# babyGroot.net
KiCad netlist of a schematic drawn in EAGLE
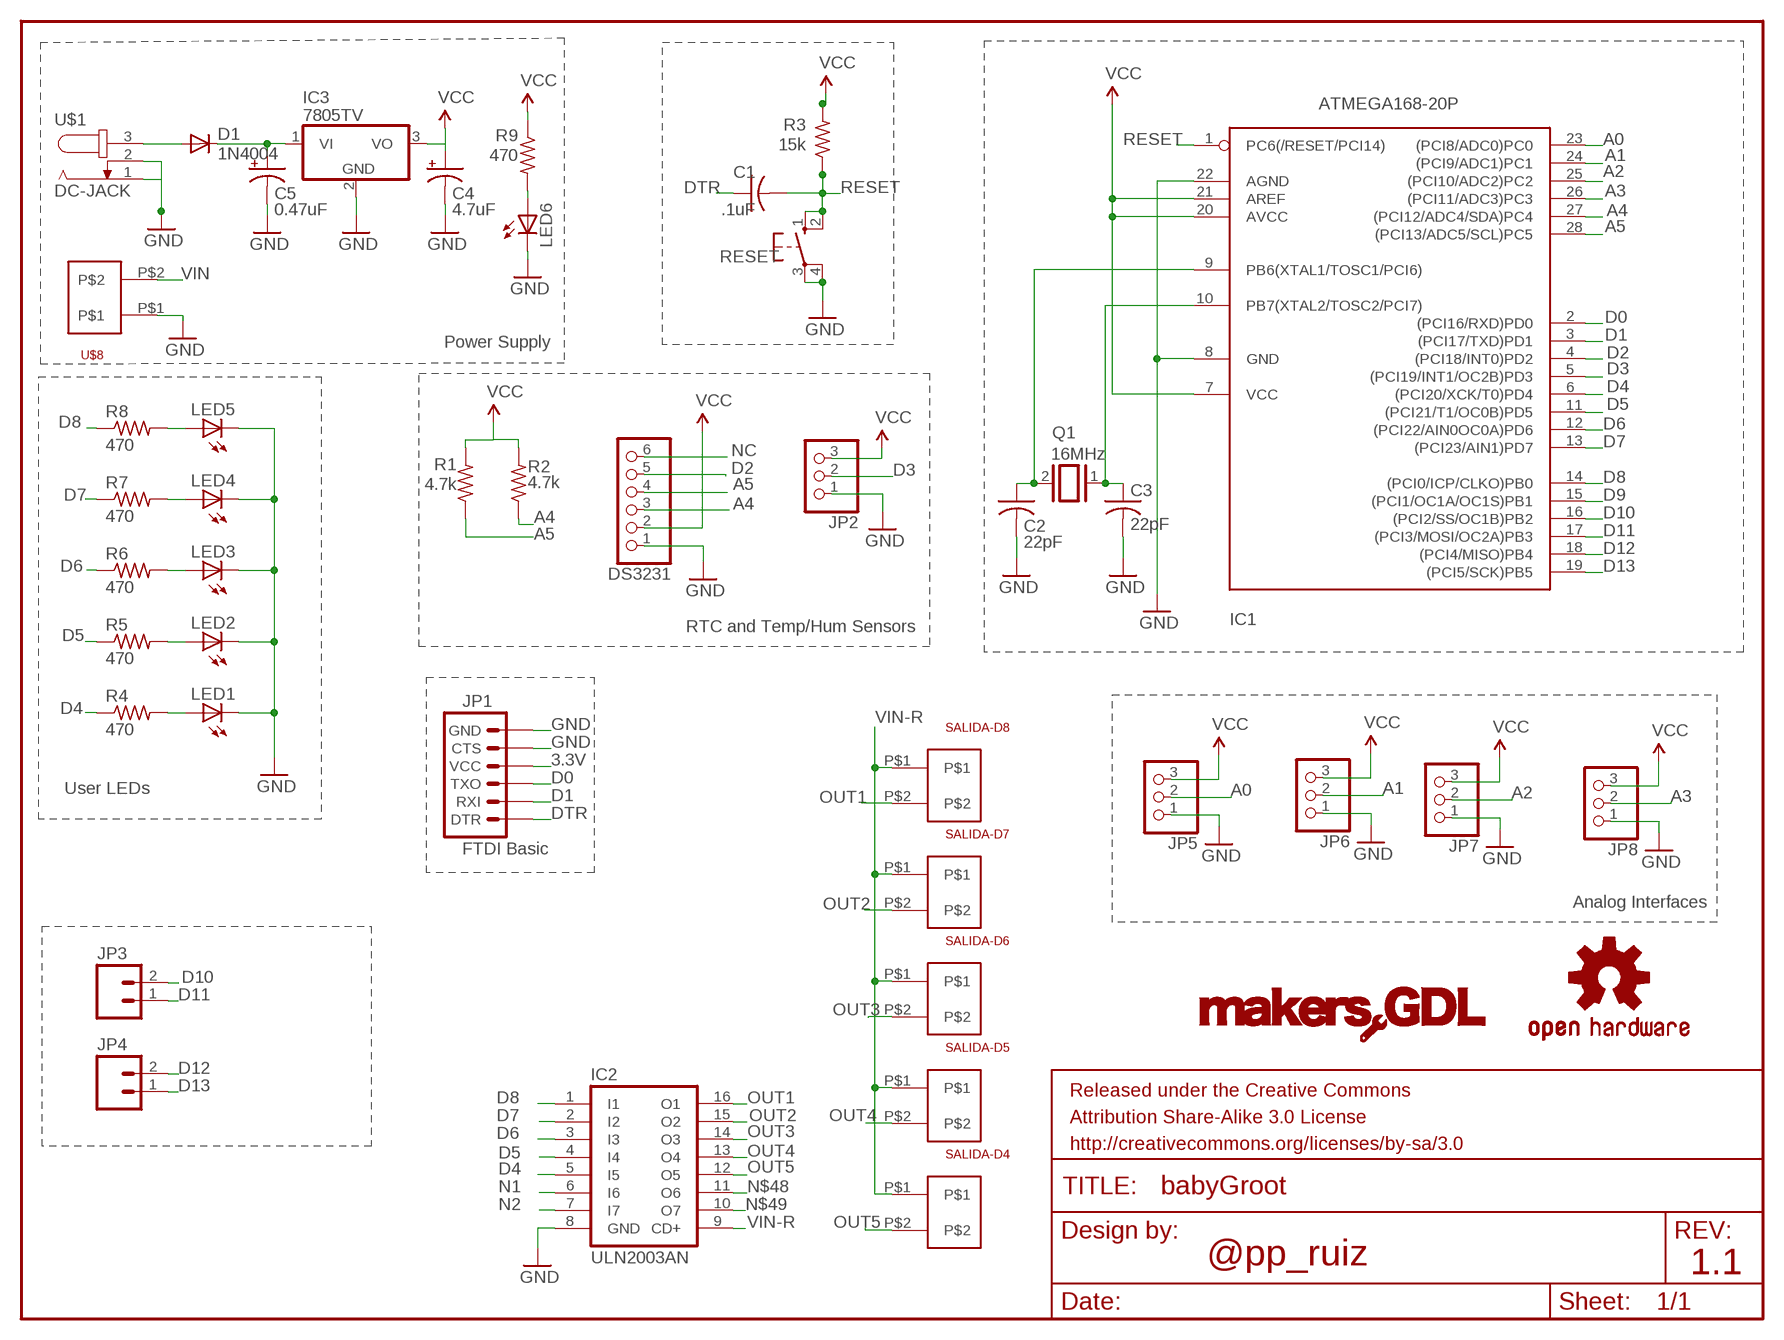
[diagram p0: schematic, sheet 1]

(export (version "E")
  (design (tool "Eeschema 10.0.6"))
  (components
    (comp (ref "C1")
      (value ".1uF")
      (footprint "eagle-import:C025-024X044")
      (libsource (lib "eagle-import") (part "C-US025-024X044"))
    )
    (comp (ref "C2")
      (value "22pF")
      (footprint "eagle-import:C025-024X044")
      (libsource (lib "eagle-import") (part "C-US025-024X044"))
    )
    (comp (ref "C3")
      (value "22pF")
      (footprint "eagle-import:C025-024X044")
      (libsource (lib "eagle-import") (part "C-US025-024X044"))
    )
    (comp (ref "C4")
      (value "4.7uF")
      (footprint "eagle-import:E2,5-6E")
      (libsource (lib "eagle-import") (part "CPOL-USE2,5-6E"))
    )
    (comp (ref "C5")
      (value "0.47uF")
      (footprint "eagle-import:E2,5-6E")
      (libsource (lib "eagle-import") (part "CPOL-USE2,5-6E"))
    )
    (comp (ref "D1")
      (value "1N4004")
      (footprint "eagle-import:DO41-10")
      (libsource (lib "eagle-import") (part "1N4004"))
    )
    (comp (ref "DS3231")
      (value "PINHD-1X6")
      (footprint "eagle-import:1X06")
      (libsource (lib "eagle-import") (part "PINHD-1X6"))
    )
    (comp (ref "FRAME1")
      (value "FRAME-LETTER")
      (footprint "eagle-import:CREATIVE_COMMONS")
      (libsource (lib "eagle-import") (part "FRAME-LETTER"))
    )
    (comp (ref "IC1")
      (value "ATMEGA168-20P")
      (footprint "eagle-import:DIL28-3")
      (libsource (lib "eagle-import") (part "ATMEGA168P-20"))
    )
    (comp (ref "IC2")
      (value "ULN2003AN")
      (footprint "eagle-import:DIL16")
      (libsource (lib "eagle-import") (part "ULN2003AN"))
    )
    (comp (ref "IC3")
      (value "7805TV")
      (footprint "eagle-import:TO220V")
      (libsource (lib "eagle-import") (part "78TV05"))
    )
    (comp (ref "JP1")
      (value "FTDI Basic")
      (footprint "eagle-import:1X06")
      (libsource (lib "eagle-import") (part "ARDUINO_SERIAL_PROGRAMPTH"))
    )
    (comp (ref "JP2")
      (value "PINHD-1X3")
      (footprint "eagle-import:1X03")
      (libsource (lib "eagle-import") (part "PINHD-1X3"))
    )
    (comp (ref "JP3")
      (value "M02PTH")
      (footprint "eagle-import:1X02")
      (libsource (lib "eagle-import") (part "M02PTH"))
    )
    (comp (ref "JP4")
      (value "M02PTH")
      (footprint "eagle-import:1X02")
      (libsource (lib "eagle-import") (part "M02PTH"))
    )
    (comp (ref "JP5")
      (value "PINHD-1X3")
      (footprint "eagle-import:1X03")
      (libsource (lib "eagle-import") (part "PINHD-1X3"))
    )
    (comp (ref "JP6")
      (value "PINHD-1X3")
      (footprint "eagle-import:1X03")
      (libsource (lib "eagle-import") (part "PINHD-1X3"))
    )
    (comp (ref "JP7")
      (value "PINHD-1X3")
      (footprint "eagle-import:1X03")
      (libsource (lib "eagle-import") (part "PINHD-1X3"))
    )
    (comp (ref "JP8")
      (value "PINHD-1X3")
      (footprint "eagle-import:1X03")
      (libsource (lib "eagle-import") (part "PINHD-1X3"))
    )
    (comp (ref "LED1")
      (value "LED3MM")
      (footprint "eagle-import:LED3MM")
      (libsource (lib "eagle-import") (part "LED3MM"))
    )
    (comp (ref "LED2")
      (value "LED3MM")
      (footprint "eagle-import:LED3MM")
      (libsource (lib "eagle-import") (part "LED3MM"))
    )
    (comp (ref "LED3")
      (value "LED3MM")
      (footprint "eagle-import:LED3MM")
      (libsource (lib "eagle-import") (part "LED3MM"))
    )
    (comp (ref "LED4")
      (value "LED3MM")
      (footprint "eagle-import:LED3MM")
      (libsource (lib "eagle-import") (part "LED3MM"))
    )
    (comp (ref "LED5")
      (value "LED3MM")
      (footprint "eagle-import:LED3MM")
      (libsource (lib "eagle-import") (part "LED3MM"))
    )
    (comp (ref "LED6")
      (value "LED3MM")
      (footprint "eagle-import:LED3MM")
      (libsource (lib "eagle-import") (part "LED3MM"))
    )
    (comp (ref "Q1")
      (value "16MHz")
      (footprint "eagle-import:QS")
      (libsource (lib "eagle-import") (part "XTAL/S"))
    )
    (comp (ref "R1")
      (value "4.7k")
      (footprint "eagle-import:0204V")
      (libsource (lib "eagle-import") (part "R-US_0204/2V"))
    )
    (comp (ref "R2")
      (value "4.7k")
      (footprint "eagle-import:0204V")
      (libsource (lib "eagle-import") (part "R-US_0204/2V"))
    )
    (comp (ref "R3")
      (value "15k")
      (footprint "eagle-import:0204V")
      (libsource (lib "eagle-import") (part "R-US_0204/2V"))
    )
    (comp (ref "R4")
      (value "470")
      (footprint "eagle-import:0204V")
      (libsource (lib "eagle-import") (part "R-US_0204/2V"))
    )
    (comp (ref "R5")
      (value "470")
      (footprint "eagle-import:0204V")
      (libsource (lib "eagle-import") (part "R-US_0204/2V"))
    )
    (comp (ref "R6")
      (value "470")
      (footprint "eagle-import:0204V")
      (libsource (lib "eagle-import") (part "R-US_0204/2V"))
    )
    (comp (ref "R7")
      (value "470")
      (footprint "eagle-import:0204V")
      (libsource (lib "eagle-import") (part "R-US_0204/2V"))
    )
    (comp (ref "R8")
      (value "470")
      (footprint "eagle-import:0204V")
      (libsource (lib "eagle-import") (part "R-US_0204/2V"))
    )
    (comp (ref "R9")
      (value "470")
      (footprint "eagle-import:0204V")
      (libsource (lib "eagle-import") (part "R-US_0204/2V"))
    )
    (comp (ref "RESET")
      (value "10-XX")
      (footprint "eagle-import:B3F-10XX")
      (fields (field (name "MPN") "B3F-1000"))
      (libsource (lib "eagle-import") (part "10-XX"))
    )
    (comp (ref "SALIDA-D4")
      (value "2POSHEADER-0.5MM")
      (footprint "eagle-import:2PIN-0.5MM")
      (libsource (lib "eagle-import") (part "2POSHEADER-0.5MM"))
    )
    (comp (ref "SALIDA-D5")
      (value "2POSHEADER-0.5MM")
      (footprint "eagle-import:2PIN-0.5MM")
      (libsource (lib "eagle-import") (part "2POSHEADER-0.5MM"))
    )
    (comp (ref "SALIDA-D6")
      (value "2POSHEADER-0.5MM")
      (footprint "eagle-import:2PIN-0.5MM")
      (libsource (lib "eagle-import") (part "2POSHEADER-0.5MM"))
    )
    (comp (ref "SALIDA-D7")
      (value "2POSHEADER-0.5MM")
      (footprint "eagle-import:2PIN-0.5MM")
      (libsource (lib "eagle-import") (part "2POSHEADER-0.5MM"))
    )
    (comp (ref "SALIDA-D8")
      (value "2POSHEADER-0.5MM")
      (footprint "eagle-import:2PIN-0.5MM")
      (libsource (lib "eagle-import") (part "2POSHEADER-0.5MM"))
    )
    (comp (ref "U$1")
      (value "DC-JACK")
      (footprint "eagle-import:SPC4078")
      (libsource (lib "eagle-import") (part "DC-JACK"))
    )
    (comp (ref "U$3")
      (value "OSHW-LOGOS")
      (footprint "eagle-import:OSHW-LOGO-S")
      (libsource (lib "eagle-import") (part "OSHW-LOGOS"))
    )
    (comp (ref "U$4")
      (value "MAKERSGDLLOGO-SMALL")
      (footprint "eagle-import:MAKERSGGL-SMALL")
      (libsource (lib "eagle-import") (part "MAKERSGDLLOGO-SMALL"))
    )
    (comp (ref "U$8")
      (value "2POSHEADER-0.5MM")
      (footprint "eagle-import:2PIN-0.5MM")
      (libsource (lib "eagle-import") (part "2POSHEADER-0.5MM"))
    )
  )
  (nets
    (net (code "1") (name "/A0") (class "Default")
      (node (ref "IC1") (pin "23") (pinfunction "(PCI8/ADC0)PC0_23") (pintype "bidirectional"))
      (node (ref "JP5") (pin "2") (pinfunction "2_2") (pintype "passive"))
    )
    (net (code "2") (name "/A1") (class "Default")
      (node (ref "IC1") (pin "24") (pinfunction "(PCI9/ADC1)PC1_24") (pintype "bidirectional"))
      (node (ref "JP6") (pin "2") (pinfunction "2_2") (pintype "passive"))
    )
    (net (code "3") (name "/A2") (class "Default")
      (node (ref "IC1") (pin "25") (pinfunction "(PCI10/ADC2)PC2_25") (pintype "bidirectional"))
      (node (ref "JP7") (pin "2") (pinfunction "2_2") (pintype "passive"))
    )
    (net (code "4") (name "/A3") (class "Default")
      (node (ref "IC1") (pin "26") (pinfunction "(PCI11/ADC3)PC3_26") (pintype "bidirectional"))
      (node (ref "JP8") (pin "2") (pinfunction "2_2") (pintype "passive"))
    )
    (net (code "5") (name "/A4") (class "Default")
      (node (ref "DS3231") (pin "3") (pinfunction "3_3") (pintype "passive"))
      (node (ref "IC1") (pin "27") (pinfunction "(PCI12/ADC4/SDA)PC4_27") (pintype "bidirectional"))
      (node (ref "R2") (pin "1") (pinfunction "1_1") (pintype "passive"))
    )
    (net (code "6") (name "/A5") (class "Default")
      (node (ref "DS3231") (pin "4") (pinfunction "4_4") (pintype "passive"))
      (node (ref "IC1") (pin "28") (pinfunction "(PCI13/ADC5/SCL)PC5_28") (pintype "bidirectional"))
      (node (ref "R1") (pin "1") (pinfunction "1_1") (pintype "passive"))
    )
    (net (code "7") (name "/D0") (class "Default")
      (node (ref "IC1") (pin "2") (pinfunction "(PCI16/RXD)PD0_2") (pintype "bidirectional"))
      (node (ref "JP1") (pin "3") (pinfunction "TXO_3") (pintype "passive"))
    )
    (net (code "8") (name "/D1") (class "Default")
      (node (ref "IC1") (pin "3") (pinfunction "(PCI17/TXD)PD1_3") (pintype "bidirectional"))
      (node (ref "JP1") (pin "2") (pinfunction "RXI_2") (pintype "passive"))
    )
    (net (code "9") (name "/D2") (class "Default")
      (node (ref "DS3231") (pin "5") (pinfunction "5_5") (pintype "passive"))
      (node (ref "IC1") (pin "4") (pinfunction "(PCI18/INT0)PD2_4") (pintype "bidirectional"))
    )
    (net (code "10") (name "/D3") (class "Default")
      (node (ref "IC1") (pin "5") (pinfunction "(PCI19/INT1/OC2B)PD3_5") (pintype "bidirectional"))
      (node (ref "JP2") (pin "2") (pinfunction "2_2") (pintype "passive"))
    )
    (net (code "11") (name "/D4") (class "Default")
      (node (ref "IC1") (pin "6") (pinfunction "(PCI20/XCK/T0)PD4_6") (pintype "bidirectional"))
      (node (ref "IC2") (pin "5") (pinfunction "I5_5") (pintype "input"))
      (node (ref "R4") (pin "1") (pinfunction "1_1") (pintype "passive"))
    )
    (net (code "12") (name "/D5") (class "Default")
      (node (ref "IC1") (pin "11") (pinfunction "(PCI21/T1/OC0B)PD5_11") (pintype "bidirectional"))
      (node (ref "IC2") (pin "4") (pinfunction "I4_4") (pintype "input"))
      (node (ref "R5") (pin "1") (pinfunction "1_1") (pintype "passive"))
    )
    (net (code "13") (name "/D6") (class "Default")
      (node (ref "IC1") (pin "12") (pinfunction "(PCI22/AIN0OC0A)PD6_12") (pintype "bidirectional"))
      (node (ref "IC2") (pin "3") (pinfunction "I3_3") (pintype "input"))
      (node (ref "R6") (pin "1") (pinfunction "1_1") (pintype "passive"))
    )
    (net (code "14") (name "/D7") (class "Default")
      (node (ref "IC1") (pin "13") (pinfunction "(PCI23/AIN1)PD7_13") (pintype "bidirectional"))
      (node (ref "IC2") (pin "2") (pinfunction "I2_2") (pintype "input"))
      (node (ref "R7") (pin "1") (pinfunction "1_1") (pintype "passive"))
    )
    (net (code "15") (name "/D8") (class "Default")
      (node (ref "IC1") (pin "14") (pinfunction "(PCI0/ICP/CLKO)PB0_14") (pintype "bidirectional"))
      (node (ref "IC2") (pin "1") (pinfunction "I1_1") (pintype "input"))
      (node (ref "R8") (pin "1") (pinfunction "1_1") (pintype "passive"))
    )
    (net (code "16") (name "/D9") (class "Default")
      (node (ref "IC1") (pin "15") (pinfunction "(PCI1/OC1A/OC1S)PB1_15") (pintype "bidirectional"))
    )
    (net (code "17") (name "/D10") (class "Default")
      (node (ref "IC1") (pin "16") (pinfunction "(PCI2/SS/OC1B)PB2_16") (pintype "bidirectional"))
      (node (ref "JP3") (pin "2") (pinfunction "2_2") (pintype "passive"))
    )
    (net (code "18") (name "/D11") (class "Default")
      (node (ref "IC1") (pin "17") (pinfunction "(PCI3/MOSI/OC2A)PB3_17") (pintype "bidirectional"))
      (node (ref "JP3") (pin "1") (pinfunction "1_1") (pintype "passive"))
    )
    (net (code "19") (name "/D12") (class "Default")
      (node (ref "IC1") (pin "18") (pinfunction "(PCI4/MISO)PB4_18") (pintype "bidirectional"))
      (node (ref "JP4") (pin "2") (pinfunction "2_2") (pintype "passive"))
    )
    (net (code "20") (name "/D13") (class "Default")
      (node (ref "IC1") (pin "19") (pinfunction "(PCI5/SCK)PB5_19") (pintype "bidirectional"))
      (node (ref "JP4") (pin "1") (pinfunction "1_1") (pintype "passive"))
    )
    (net (code "21") (name "/DTR") (class "Default")
      (node (ref "C1") (pin "1") (pinfunction "1_1") (pintype "passive"))
      (node (ref "JP1") (pin "1") (pinfunction "DTR_1") (pintype "passive"))
    )
    (net (code "22") (name "/N$48") (class "Default")
      (node (ref "IC2") (pin "11") (pinfunction "O6_11") (pintype "open_collector"))
    )
    (net (code "23") (name "/N$49") (class "Default")
      (node (ref "IC2") (pin "10") (pinfunction "O7_10") (pintype "open_collector"))
    )
    (net (code "24") (name "/N1") (class "Default")
      (node (ref "IC2") (pin "6") (pinfunction "I6_6") (pintype "input"))
    )
    (net (code "25") (name "/N2") (class "Default")
      (node (ref "IC2") (pin "7") (pinfunction "I7_7") (pintype "input"))
    )
    (net (code "26") (name "/NC") (class "Default")
      (node (ref "DS3231") (pin "6") (pinfunction "6_6") (pintype "passive"))
    )
    (net (code "27") (name "/OUT1") (class "Default")
      (node (ref "IC2") (pin "16") (pinfunction "O1_16") (pintype "open_collector"))
      (node (ref "SALIDA-D8") (pin "P$2") (pinfunction "P$2_P$2") (pintype "bidirectional"))
    )
    (net (code "28") (name "/OUT2") (class "Default")
      (node (ref "IC2") (pin "15") (pinfunction "O2_15") (pintype "open_collector"))
      (node (ref "SALIDA-D7") (pin "P$2") (pinfunction "P$2_P$2") (pintype "bidirectional"))
    )
    (net (code "29") (name "/OUT3") (class "Default")
      (node (ref "IC2") (pin "14") (pinfunction "O3_14") (pintype "open_collector"))
      (node (ref "SALIDA-D6") (pin "P$2") (pinfunction "P$2_P$2") (pintype "bidirectional"))
    )
    (net (code "30") (name "/OUT4") (class "Default")
      (node (ref "IC2") (pin "13") (pinfunction "O4_13") (pintype "open_collector"))
      (node (ref "SALIDA-D5") (pin "P$2") (pinfunction "P$2_P$2") (pintype "bidirectional"))
    )
    (net (code "31") (name "/OUT5") (class "Default")
      (node (ref "IC2") (pin "12") (pinfunction "O5_12") (pintype "open_collector"))
      (node (ref "SALIDA-D4") (pin "P$2") (pinfunction "P$2_P$2") (pintype "bidirectional"))
    )
    (net (code "32") (name "/RESET") (class "Default")
      (node (ref "C1") (pin "2") (pinfunction "2_2") (pintype "passive"))
      (node (ref "IC1") (pin "1") (pinfunction "PC6(/RESET/PCI14)_1") (pintype "bidirectional"))
      (node (ref "R3") (pin "1") (pinfunction "1_1") (pintype "passive"))
      (node (ref "RESET") (pin "1") (pinfunction "S_1") (pintype "passive"))
      (node (ref "RESET") (pin "2") (pinfunction "S1_2") (pintype "passive"))
    )
    (net (code "33") (name "/VIN") (class "Default")
      (node (ref "D1") (pin "A") (pinfunction "A_A") (pintype "passive"))
      (node (ref "U$1") (pin "3") (pinfunction "3_3") (pintype "passive"))
      (node (ref "U$8") (pin "P$2") (pinfunction "P$2_P$2") (pintype "bidirectional"))
    )
    (net (code "34") (name "/VIN-R") (class "Default")
      (node (ref "C5") (pin "+") (pinfunction "+_+") (pintype "passive"))
      (node (ref "D1") (pin "C") (pinfunction "C_C") (pintype "passive"))
      (node (ref "IC2") (pin "9") (pinfunction "CD+_9") (pintype "passive"))
      (node (ref "IC3") (pin "1") (pinfunction "VI_1") (pintype "input"))
      (node (ref "SALIDA-D4") (pin "P$1") (pinfunction "P$1_P$1") (pintype "bidirectional"))
      (node (ref "SALIDA-D5") (pin "P$1") (pinfunction "P$1_P$1") (pintype "bidirectional"))
      (node (ref "SALIDA-D6") (pin "P$1") (pinfunction "P$1_P$1") (pintype "bidirectional"))
      (node (ref "SALIDA-D7") (pin "P$1") (pinfunction "P$1_P$1") (pintype "bidirectional"))
      (node (ref "SALIDA-D8") (pin "P$1") (pinfunction "P$1_P$1") (pintype "bidirectional"))
    )
    (net (code "35") (name "GND") (class "Default")
      (node (ref "C2") (pin "2") (pinfunction "2_2") (pintype "passive"))
      (node (ref "C3") (pin "2") (pinfunction "2_2") (pintype "passive"))
      (node (ref "C4") (pin "-") (pinfunction "-_-") (pintype "passive"))
      (node (ref "C5") (pin "-") (pinfunction "-_-") (pintype "passive"))
      (node (ref "DS3231") (pin "1") (pinfunction "1_1") (pintype "passive"))
      (node (ref "IC1") (pin "22") (pinfunction "AGND_22") (pintype "bidirectional"))
      (node (ref "IC1") (pin "8") (pinfunction "GND_8") (pintype "bidirectional"))
      (node (ref "IC2") (pin "8") (pinfunction "GND_8") (pintype "power_in"))
      (node (ref "IC3") (pin "2") (pinfunction "GND_2") (pintype "passive"))
      (node (ref "JP1") (pin "5") (pinfunction "CTS_5") (pintype "passive"))
      (node (ref "JP1") (pin "6") (pinfunction "GND_6") (pintype "passive"))
      (node (ref "JP2") (pin "1") (pinfunction "1_1") (pintype "passive"))
      (node (ref "JP5") (pin "1") (pinfunction "1_1") (pintype "passive"))
      (node (ref "JP6") (pin "1") (pinfunction "1_1") (pintype "passive"))
      (node (ref "JP7") (pin "1") (pinfunction "1_1") (pintype "passive"))
      (node (ref "JP8") (pin "1") (pinfunction "1_1") (pintype "passive"))
      (node (ref "LED1") (pin "K") (pinfunction "C_K") (pintype "passive"))
      (node (ref "LED2") (pin "K") (pinfunction "C_K") (pintype "passive"))
      (node (ref "LED3") (pin "K") (pinfunction "C_K") (pintype "passive"))
      (node (ref "LED4") (pin "K") (pinfunction "C_K") (pintype "passive"))
      (node (ref "LED5") (pin "K") (pinfunction "C_K") (pintype "passive"))
      (node (ref "LED6") (pin "K") (pinfunction "C_K") (pintype "passive"))
      (node (ref "RESET") (pin "3") (pinfunction "P_3") (pintype "passive"))
      (node (ref "RESET") (pin "4") (pinfunction "P1_4") (pintype "passive"))
      (node (ref "U$1") (pin "1") (pinfunction "1_1") (pintype "passive"))
      (node (ref "U$1") (pin "2") (pinfunction "2_2") (pintype "passive"))
      (node (ref "U$8") (pin "P$1") (pinfunction "P$1_P$1") (pintype "bidirectional"))
    )
    (net (code "36") (name "Net-(IC1-PB6(XTAL1{slash}TOSC1{slash}PCI6))") (class "Default")
      (node (ref "C2") (pin "1") (pinfunction "1_1") (pintype "passive"))
      (node (ref "IC1") (pin "9") (pinfunction "PB6(XTAL1/TOSC1/PCI6)_9") (pintype "bidirectional"))
      (node (ref "Q1") (pin "2") (pinfunction "2_2") (pintype "passive"))
    )
    (net (code "37") (name "Net-(IC1-PB7(XTAL2{slash}TOSC2{slash}PCI7))") (class "Default")
      (node (ref "C3") (pin "1") (pinfunction "1_1") (pintype "passive"))
      (node (ref "IC1") (pin "10") (pinfunction "PB7(XTAL2/TOSC2/PCI7)_10") (pintype "bidirectional"))
      (node (ref "Q1") (pin "1") (pinfunction "1_1") (pintype "passive"))
    )
    (net (code "38") (name "Net-(LED1-PadA)") (class "Default")
      (node (ref "LED1") (pin "A") (pinfunction "A_A") (pintype "passive"))
      (node (ref "R4") (pin "2") (pinfunction "2_2") (pintype "passive"))
    )
    (net (code "39") (name "Net-(LED2-PadA)") (class "Default")
      (node (ref "LED2") (pin "A") (pinfunction "A_A") (pintype "passive"))
      (node (ref "R5") (pin "2") (pinfunction "2_2") (pintype "passive"))
    )
    (net (code "40") (name "Net-(LED3-PadA)") (class "Default")
      (node (ref "LED3") (pin "A") (pinfunction "A_A") (pintype "passive"))
      (node (ref "R6") (pin "2") (pinfunction "2_2") (pintype "passive"))
    )
    (net (code "41") (name "Net-(LED4-PadA)") (class "Default")
      (node (ref "LED4") (pin "A") (pinfunction "A_A") (pintype "passive"))
      (node (ref "R7") (pin "2") (pinfunction "2_2") (pintype "passive"))
    )
    (net (code "42") (name "Net-(LED5-PadA)") (class "Default")
      (node (ref "LED5") (pin "A") (pinfunction "A_A") (pintype "passive"))
      (node (ref "R8") (pin "2") (pinfunction "2_2") (pintype "passive"))
    )
    (net (code "43") (name "Net-(LED6-PadA)") (class "Default")
      (node (ref "LED6") (pin "A") (pinfunction "A_A") (pintype "passive"))
      (node (ref "R9") (pin "2") (pinfunction "2_2") (pintype "passive"))
    )
    (net (code "44") (name "VCC") (class "Default")
      (node (ref "C4") (pin "+") (pinfunction "+_+") (pintype "passive"))
      (node (ref "DS3231") (pin "2") (pinfunction "2_2") (pintype "passive"))
      (node (ref "IC1") (pin "20") (pinfunction "AVCC_20") (pintype "bidirectional"))
      (node (ref "IC1") (pin "21") (pinfunction "AREF_21") (pintype "bidirectional"))
      (node (ref "IC1") (pin "7") (pinfunction "VCC_7") (pintype "bidirectional"))
      (node (ref "IC3") (pin "3") (pinfunction "VO_3") (pintype "passive"))
      (node (ref "JP1") (pin "4") (pinfunction "VCC_4") (pintype "passive"))
      (node (ref "JP2") (pin "3") (pinfunction "3_3") (pintype "passive"))
      (node (ref "JP5") (pin "3") (pinfunction "3_3") (pintype "passive"))
      (node (ref "JP6") (pin "3") (pinfunction "3_3") (pintype "passive"))
      (node (ref "JP7") (pin "3") (pinfunction "3_3") (pintype "passive"))
      (node (ref "JP8") (pin "3") (pinfunction "3_3") (pintype "passive"))
      (node (ref "R1") (pin "2") (pinfunction "2_2") (pintype "passive"))
      (node (ref "R2") (pin "2") (pinfunction "2_2") (pintype "passive"))
      (node (ref "R3") (pin "2") (pinfunction "2_2") (pintype "passive"))
      (node (ref "R9") (pin "1") (pinfunction "1_1") (pintype "passive"))
    )
  )
)
